# LED_ROWS.net
KiCad netlist of a schematic drawn in Altium Designer
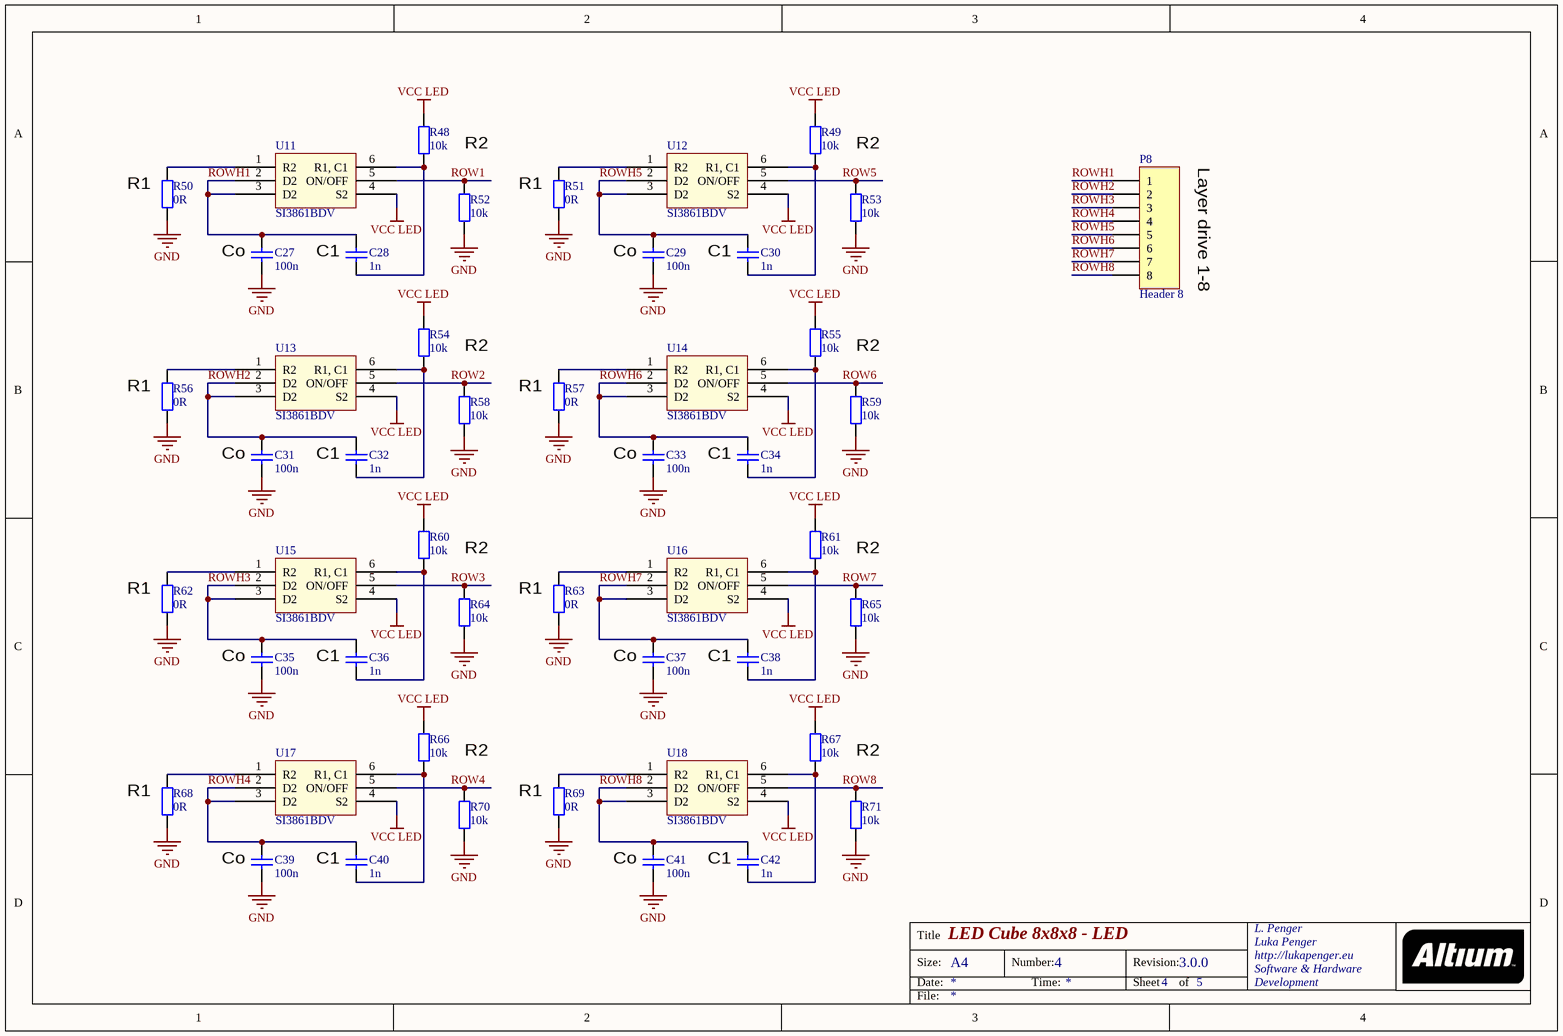
[diagram p0: LED_ROWS.SchDoc]

(export (version "E")
  (design (tool "Eeschema 10.0.6"))
  (components
    (comp (ref "C27")
      (value "100n")
      (footprint "1608[0603]")
      (description "Capacitor")
      (fields (field (name "PUBLISHER") "Altium Limited"))
      (libsource (lib "Miscellaneous Devices") (part "Cap"))
    )
    (comp (ref "C28")
      (value "1n")
      (footprint "1608[0603]")
      (description "Capacitor")
      (fields (field (name "PUBLISHER") "Altium Limited"))
      (libsource (lib "Miscellaneous Devices") (part "Cap"))
    )
    (comp (ref "C29")
      (value "100n")
      (footprint "1608[0603]")
      (description "Capacitor")
      (fields (field (name "PUBLISHER") "Altium Limited"))
      (libsource (lib "Miscellaneous Devices") (part "Cap"))
    )
    (comp (ref "C30")
      (value "1n")
      (footprint "1608[0603]")
      (description "Capacitor")
      (fields (field (name "PUBLISHER") "Altium Limited"))
      (libsource (lib "Miscellaneous Devices") (part "Cap"))
    )
    (comp (ref "C31")
      (value "100n")
      (footprint "1608[0603]")
      (description "Capacitor")
      (fields (field (name "PUBLISHER") "Altium Limited"))
      (libsource (lib "Miscellaneous Devices") (part "Cap"))
    )
    (comp (ref "C32")
      (value "1n")
      (footprint "1608[0603]")
      (description "Capacitor")
      (fields (field (name "PUBLISHER") "Altium Limited"))
      (libsource (lib "Miscellaneous Devices") (part "Cap"))
    )
    (comp (ref "C33")
      (value "100n")
      (footprint "1608[0603]")
      (description "Capacitor")
      (fields (field (name "PUBLISHER") "Altium Limited"))
      (libsource (lib "Miscellaneous Devices") (part "Cap"))
    )
    (comp (ref "C34")
      (value "1n")
      (footprint "1608[0603]")
      (description "Capacitor")
      (fields (field (name "PUBLISHER") "Altium Limited"))
      (libsource (lib "Miscellaneous Devices") (part "Cap"))
    )
    (comp (ref "C35")
      (value "100n")
      (footprint "1608[0603]")
      (description "Capacitor")
      (fields (field (name "PUBLISHER") "Altium Limited"))
      (libsource (lib "Miscellaneous Devices") (part "Cap"))
    )
    (comp (ref "C36")
      (value "1n")
      (footprint "1608[0603]")
      (description "Capacitor")
      (fields (field (name "PUBLISHER") "Altium Limited"))
      (libsource (lib "Miscellaneous Devices") (part "Cap"))
    )
    (comp (ref "C37")
      (value "100n")
      (footprint "1608[0603]")
      (description "Capacitor")
      (fields (field (name "PUBLISHER") "Altium Limited"))
      (libsource (lib "Miscellaneous Devices") (part "Cap"))
    )
    (comp (ref "C38")
      (value "1n")
      (footprint "1608[0603]")
      (description "Capacitor")
      (fields (field (name "PUBLISHER") "Altium Limited"))
      (libsource (lib "Miscellaneous Devices") (part "Cap"))
    )
    (comp (ref "C39")
      (value "100n")
      (footprint "1608[0603]")
      (description "Capacitor")
      (fields (field (name "PUBLISHER") "Altium Limited"))
      (libsource (lib "Miscellaneous Devices") (part "Cap"))
    )
    (comp (ref "C40")
      (value "1n")
      (footprint "1608[0603]")
      (description "Capacitor")
      (fields (field (name "PUBLISHER") "Altium Limited"))
      (libsource (lib "Miscellaneous Devices") (part "Cap"))
    )
    (comp (ref "C41")
      (value "100n")
      (footprint "1608[0603]")
      (description "Capacitor")
      (fields (field (name "PUBLISHER") "Altium Limited"))
      (libsource (lib "Miscellaneous Devices") (part "Cap"))
    )
    (comp (ref "C42")
      (value "1n")
      (footprint "1608[0603]")
      (description "Capacitor")
      (fields (field (name "PUBLISHER") "Altium Limited"))
      (libsource (lib "Miscellaneous Devices") (part "Cap"))
    )
    (comp (ref "P8")
      (value "Header 8")
      (footprint "IDC-2x4")
      (description "Header, 8-Pin")
      (fields (field (name "PUBLISHER") "Altium Limited"))
      (libsource (lib "Miscellaneous Connectors") (part "Header 8"))
    )
    (comp (ref "R48")
      (value "10k")
      (footprint "1608[0603]")
      (description "Resistor")
      (fields (field (name "PUBLISHER") "Altium Limited"))
      (libsource (lib "") (part "Res2_1"))
    )
    (comp (ref "R49")
      (value "10k")
      (footprint "1608[0603]")
      (description "Resistor")
      (fields (field (name "PUBLISHER") "Altium Limited"))
      (libsource (lib "") (part "Res2_1"))
    )
    (comp (ref "R50")
      (value "0R")
      (footprint "1608[0603]")
      (description "Resistor")
      (fields (field (name "PUBLISHER") "Altium Limited"))
      (libsource (lib "Miscellaneous Devices") (part "Res2"))
    )
    (comp (ref "R51")
      (value "0R")
      (footprint "1608[0603]")
      (description "Resistor")
      (fields (field (name "PUBLISHER") "Altium Limited"))
      (libsource (lib "Miscellaneous Devices") (part "Res2"))
    )
    (comp (ref "R52")
      (value "10k")
      (footprint "1608[0603]")
      (description "Resistor")
      (fields (field (name "PUBLISHER") "Altium Limited"))
      (libsource (lib "") (part "Res2_1"))
    )
    (comp (ref "R53")
      (value "10k")
      (footprint "1608[0603]")
      (description "Resistor")
      (fields (field (name "PUBLISHER") "Altium Limited"))
      (libsource (lib "") (part "Res2_1"))
    )
    (comp (ref "R54")
      (value "10k")
      (footprint "1608[0603]")
      (description "Resistor")
      (fields (field (name "PUBLISHER") "Altium Limited"))
      (libsource (lib "") (part "Res2_1"))
    )
    (comp (ref "R55")
      (value "10k")
      (footprint "1608[0603]")
      (description "Resistor")
      (fields (field (name "PUBLISHER") "Altium Limited"))
      (libsource (lib "") (part "Res2_1"))
    )
    (comp (ref "R56")
      (value "0R")
      (footprint "1608[0603]")
      (description "Resistor")
      (fields (field (name "PUBLISHER") "Altium Limited"))
      (libsource (lib "Miscellaneous Devices") (part "Res2"))
    )
    (comp (ref "R57")
      (value "0R")
      (footprint "1608[0603]")
      (description "Resistor")
      (fields (field (name "PUBLISHER") "Altium Limited"))
      (libsource (lib "Miscellaneous Devices") (part "Res2"))
    )
    (comp (ref "R58")
      (value "10k")
      (footprint "1608[0603]")
      (description "Resistor")
      (fields (field (name "PUBLISHER") "Altium Limited"))
      (libsource (lib "") (part "Res2_1"))
    )
    (comp (ref "R59")
      (value "10k")
      (footprint "1608[0603]")
      (description "Resistor")
      (fields (field (name "PUBLISHER") "Altium Limited"))
      (libsource (lib "") (part "Res2_1"))
    )
    (comp (ref "R60")
      (value "10k")
      (footprint "1608[0603]")
      (description "Resistor")
      (fields (field (name "PUBLISHER") "Altium Limited"))
      (libsource (lib "") (part "Res2_1"))
    )
    (comp (ref "R61")
      (value "10k")
      (footprint "1608[0603]")
      (description "Resistor")
      (fields (field (name "PUBLISHER") "Altium Limited"))
      (libsource (lib "") (part "Res2_1"))
    )
    (comp (ref "R62")
      (value "0R")
      (footprint "1608[0603]")
      (description "Resistor")
      (fields (field (name "PUBLISHER") "Altium Limited"))
      (libsource (lib "Miscellaneous Devices") (part "Res2"))
    )
    (comp (ref "R63")
      (value "0R")
      (footprint "1608[0603]")
      (description "Resistor")
      (fields (field (name "PUBLISHER") "Altium Limited"))
      (libsource (lib "Miscellaneous Devices") (part "Res2"))
    )
    (comp (ref "R64")
      (value "10k")
      (footprint "1608[0603]")
      (description "Resistor")
      (fields (field (name "PUBLISHER") "Altium Limited"))
      (libsource (lib "") (part "Res2_1"))
    )
    (comp (ref "R65")
      (value "10k")
      (footprint "1608[0603]")
      (description "Resistor")
      (fields (field (name "PUBLISHER") "Altium Limited"))
      (libsource (lib "") (part "Res2_1"))
    )
    (comp (ref "R66")
      (value "10k")
      (footprint "1608[0603]")
      (description "Resistor")
      (fields (field (name "PUBLISHER") "Altium Limited"))
      (libsource (lib "") (part "Res2_1"))
    )
    (comp (ref "R67")
      (value "10k")
      (footprint "1608[0603]")
      (description "Resistor")
      (fields (field (name "PUBLISHER") "Altium Limited"))
      (libsource (lib "") (part "Res2_1"))
    )
    (comp (ref "R68")
      (value "0R")
      (footprint "1608[0603]")
      (description "Resistor")
      (fields (field (name "PUBLISHER") "Altium Limited"))
      (libsource (lib "Miscellaneous Devices") (part "Res2"))
    )
    (comp (ref "R69")
      (value "0R")
      (footprint "1608[0603]")
      (description "Resistor")
      (fields (field (name "PUBLISHER") "Altium Limited"))
      (libsource (lib "Miscellaneous Devices") (part "Res2"))
    )
    (comp (ref "R70")
      (value "10k")
      (footprint "1608[0603]")
      (description "Resistor")
      (fields (field (name "PUBLISHER") "Altium Limited"))
      (libsource (lib "") (part "Res2_1"))
    )
    (comp (ref "R71")
      (value "10k")
      (footprint "1608[0603]")
      (description "Resistor")
      (fields (field (name "PUBLISHER") "Altium Limited"))
      (libsource (lib "") (part "Res2_1"))
    )
    (comp (ref "U11")
      (value "SI3861BDV")
      (footprint "TSOP 6")
      (description "4.5 - 20V 2.3A Load Switch")
      (libsource (lib "LukaLIBRARY") (part "SI3861BDV"))
    )
    (comp (ref "U12")
      (value "SI3861BDV")
      (footprint "TSOP 6")
      (description "4.5 - 20V 2.3A Load Switch")
      (libsource (lib "LukaLIBRARY") (part "SI3861BDV"))
    )
    (comp (ref "U13")
      (value "SI3861BDV")
      (footprint "TSOP 6")
      (description "4.5 - 20V 2.3A Load Switch")
      (libsource (lib "LukaLIBRARY") (part "SI3861BDV"))
    )
    (comp (ref "U14")
      (value "SI3861BDV")
      (footprint "TSOP 6")
      (description "4.5 - 20V 2.3A Load Switch")
      (libsource (lib "LukaLIBRARY") (part "SI3861BDV"))
    )
    (comp (ref "U15")
      (value "SI3861BDV")
      (footprint "TSOP 6")
      (description "4.5 - 20V 2.3A Load Switch")
      (libsource (lib "LukaLIBRARY") (part "SI3861BDV"))
    )
    (comp (ref "U16")
      (value "SI3861BDV")
      (footprint "TSOP 6")
      (description "4.5 - 20V 2.3A Load Switch")
      (libsource (lib "LukaLIBRARY") (part "SI3861BDV"))
    )
    (comp (ref "U17")
      (value "SI3861BDV")
      (footprint "TSOP 6")
      (description "4.5 - 20V 2.3A Load Switch")
      (libsource (lib "LukaLIBRARY") (part "SI3861BDV"))
    )
    (comp (ref "U18")
      (value "SI3861BDV")
      (footprint "TSOP 6")
      (description "4.5 - 20V 2.3A Load Switch")
      (libsource (lib "LukaLIBRARY") (part "SI3861BDV"))
    )
  )
  (nets
    (net (code "1") (name "/ROW1") (class "Default")
      (node (ref "R52") (pin "2") (pinfunction "2_2") (pintype "passive"))
      (node (ref "U11") (pin "5") (pinfunction "ON/OFF_5") (pintype "passive"))
    )
    (net (code "2") (name "/ROW2") (class "Default")
      (node (ref "R58") (pin "2") (pinfunction "2_2") (pintype "passive"))
      (node (ref "U13") (pin "5") (pinfunction "ON/OFF_5") (pintype "passive"))
    )
    (net (code "3") (name "/ROW3") (class "Default")
      (node (ref "R64") (pin "2") (pinfunction "2_2") (pintype "passive"))
      (node (ref "U15") (pin "5") (pinfunction "ON/OFF_5") (pintype "passive"))
    )
    (net (code "4") (name "/ROW4") (class "Default")
      (node (ref "R70") (pin "2") (pinfunction "2_2") (pintype "passive"))
      (node (ref "U17") (pin "5") (pinfunction "ON/OFF_5") (pintype "passive"))
    )
    (net (code "5") (name "/ROW5") (class "Default")
      (node (ref "R53") (pin "2") (pinfunction "2_2") (pintype "passive"))
      (node (ref "U12") (pin "5") (pinfunction "ON/OFF_5") (pintype "passive"))
    )
    (net (code "6") (name "/ROW6") (class "Default")
      (node (ref "R59") (pin "2") (pinfunction "2_2") (pintype "passive"))
      (node (ref "U14") (pin "5") (pinfunction "ON/OFF_5") (pintype "passive"))
    )
    (net (code "7") (name "/ROW7") (class "Default")
      (node (ref "R65") (pin "2") (pinfunction "2_2") (pintype "passive"))
      (node (ref "U16") (pin "5") (pinfunction "ON/OFF_5") (pintype "passive"))
    )
    (net (code "8") (name "/ROW8") (class "Default")
      (node (ref "R71") (pin "2") (pinfunction "2_2") (pintype "passive"))
      (node (ref "U18") (pin "5") (pinfunction "ON/OFF_5") (pintype "passive"))
    )
    (net (code "9") (name "/ROWH1") (class "Default")
      (node (ref "C27") (pin "1") (pinfunction "1_1") (pintype "passive"))
      (node (ref "C28") (pin "1") (pinfunction "1_1") (pintype "passive"))
      (node (ref "P8") (pin "1") (pinfunction "1_1") (pintype "passive"))
      (node (ref "U11") (pin "2") (pinfunction "D2_2") (pintype "passive"))
      (node (ref "U11") (pin "3") (pinfunction "D2_3") (pintype "passive"))
    )
    (net (code "10") (name "/ROWH2") (class "Default")
      (node (ref "C31") (pin "1") (pinfunction "1_1") (pintype "passive"))
      (node (ref "C32") (pin "1") (pinfunction "1_1") (pintype "passive"))
      (node (ref "P8") (pin "2") (pinfunction "2_2") (pintype "passive"))
      (node (ref "U13") (pin "2") (pinfunction "D2_2") (pintype "passive"))
      (node (ref "U13") (pin "3") (pinfunction "D2_3") (pintype "passive"))
    )
    (net (code "11") (name "/ROWH3") (class "Default")
      (node (ref "C35") (pin "1") (pinfunction "1_1") (pintype "passive"))
      (node (ref "C36") (pin "1") (pinfunction "1_1") (pintype "passive"))
      (node (ref "P8") (pin "3") (pinfunction "3_3") (pintype "passive"))
      (node (ref "U15") (pin "2") (pinfunction "D2_2") (pintype "passive"))
      (node (ref "U15") (pin "3") (pinfunction "D2_3") (pintype "passive"))
    )
    (net (code "12") (name "/ROWH4") (class "Default")
      (node (ref "C39") (pin "1") (pinfunction "1_1") (pintype "passive"))
      (node (ref "C40") (pin "1") (pinfunction "1_1") (pintype "passive"))
      (node (ref "P8") (pin "4") (pinfunction "4_4") (pintype "passive"))
      (node (ref "U17") (pin "2") (pinfunction "D2_2") (pintype "passive"))
      (node (ref "U17") (pin "3") (pinfunction "D2_3") (pintype "passive"))
    )
    (net (code "13") (name "/ROWH5") (class "Default")
      (node (ref "C29") (pin "1") (pinfunction "1_1") (pintype "passive"))
      (node (ref "C30") (pin "1") (pinfunction "1_1") (pintype "passive"))
      (node (ref "P8") (pin "5") (pinfunction "5_5") (pintype "passive"))
      (node (ref "U12") (pin "2") (pinfunction "D2_2") (pintype "passive"))
      (node (ref "U12") (pin "3") (pinfunction "D2_3") (pintype "passive"))
    )
    (net (code "14") (name "/ROWH6") (class "Default")
      (node (ref "C33") (pin "1") (pinfunction "1_1") (pintype "passive"))
      (node (ref "C34") (pin "1") (pinfunction "1_1") (pintype "passive"))
      (node (ref "P8") (pin "6") (pinfunction "6_6") (pintype "passive"))
      (node (ref "U14") (pin "2") (pinfunction "D2_2") (pintype "passive"))
      (node (ref "U14") (pin "3") (pinfunction "D2_3") (pintype "passive"))
    )
    (net (code "15") (name "/ROWH7") (class "Default")
      (node (ref "C37") (pin "1") (pinfunction "1_1") (pintype "passive"))
      (node (ref "C38") (pin "1") (pinfunction "1_1") (pintype "passive"))
      (node (ref "P8") (pin "7") (pinfunction "7_7") (pintype "passive"))
      (node (ref "U16") (pin "2") (pinfunction "D2_2") (pintype "passive"))
      (node (ref "U16") (pin "3") (pinfunction "D2_3") (pintype "passive"))
    )
    (net (code "16") (name "/ROWH8") (class "Default")
      (node (ref "C41") (pin "1") (pinfunction "1_1") (pintype "passive"))
      (node (ref "C42") (pin "1") (pinfunction "1_1") (pintype "passive"))
      (node (ref "P8") (pin "8") (pinfunction "8_8") (pintype "passive"))
      (node (ref "U18") (pin "2") (pinfunction "D2_2") (pintype "passive"))
      (node (ref "U18") (pin "3") (pinfunction "D2_3") (pintype "passive"))
    )
    (net (code "17") (name "GND") (class "Default")
      (node (ref "C27") (pin "2") (pinfunction "2_2") (pintype "passive"))
      (node (ref "C29") (pin "2") (pinfunction "2_2") (pintype "passive"))
      (node (ref "C31") (pin "2") (pinfunction "2_2") (pintype "passive"))
      (node (ref "C33") (pin "2") (pinfunction "2_2") (pintype "passive"))
      (node (ref "C35") (pin "2") (pinfunction "2_2") (pintype "passive"))
      (node (ref "C37") (pin "2") (pinfunction "2_2") (pintype "passive"))
      (node (ref "C39") (pin "2") (pinfunction "2_2") (pintype "passive"))
      (node (ref "C41") (pin "2") (pinfunction "2_2") (pintype "passive"))
      (node (ref "R50") (pin "2") (pinfunction "2_2") (pintype "passive"))
      (node (ref "R51") (pin "2") (pinfunction "2_2") (pintype "passive"))
      (node (ref "R52") (pin "1") (pinfunction "1_1") (pintype "passive"))
      (node (ref "R53") (pin "1") (pinfunction "1_1") (pintype "passive"))
      (node (ref "R56") (pin "2") (pinfunction "2_2") (pintype "passive"))
      (node (ref "R57") (pin "2") (pinfunction "2_2") (pintype "passive"))
      (node (ref "R58") (pin "1") (pinfunction "1_1") (pintype "passive"))
      (node (ref "R59") (pin "1") (pinfunction "1_1") (pintype "passive"))
      (node (ref "R62") (pin "2") (pinfunction "2_2") (pintype "passive"))
      (node (ref "R63") (pin "2") (pinfunction "2_2") (pintype "passive"))
      (node (ref "R64") (pin "1") (pinfunction "1_1") (pintype "passive"))
      (node (ref "R65") (pin "1") (pinfunction "1_1") (pintype "passive"))
      (node (ref "R68") (pin "2") (pinfunction "2_2") (pintype "passive"))
      (node (ref "R69") (pin "2") (pinfunction "2_2") (pintype "passive"))
      (node (ref "R70") (pin "1") (pinfunction "1_1") (pintype "passive"))
      (node (ref "R71") (pin "1") (pinfunction "1_1") (pintype "passive"))
    )
    (net (code "18") (name "Net-(U11-R1,_C1)") (class "Default")
      (node (ref "C28") (pin "2") (pinfunction "2_2") (pintype "passive"))
      (node (ref "R48") (pin "1") (pinfunction "1_1") (pintype "passive"))
      (node (ref "U11") (pin "6") (pinfunction "R1,_C1_6") (pintype "passive"))
    )
    (net (code "19") (name "Net-(U11-R2)") (class "Default")
      (node (ref "R50") (pin "1") (pinfunction "1_1") (pintype "passive"))
      (node (ref "U11") (pin "1") (pinfunction "R2_1") (pintype "passive"))
    )
    (net (code "20") (name "Net-(U12-R1,_C1)") (class "Default")
      (node (ref "C30") (pin "2") (pinfunction "2_2") (pintype "passive"))
      (node (ref "R49") (pin "1") (pinfunction "1_1") (pintype "passive"))
      (node (ref "U12") (pin "6") (pinfunction "R1,_C1_6") (pintype "passive"))
    )
    (net (code "21") (name "Net-(U12-R2)") (class "Default")
      (node (ref "R51") (pin "1") (pinfunction "1_1") (pintype "passive"))
      (node (ref "U12") (pin "1") (pinfunction "R2_1") (pintype "passive"))
    )
    (net (code "22") (name "Net-(U13-R1,_C1)") (class "Default")
      (node (ref "C32") (pin "2") (pinfunction "2_2") (pintype "passive"))
      (node (ref "R54") (pin "1") (pinfunction "1_1") (pintype "passive"))
      (node (ref "U13") (pin "6") (pinfunction "R1,_C1_6") (pintype "passive"))
    )
    (net (code "23") (name "Net-(U13-R2)") (class "Default")
      (node (ref "R56") (pin "1") (pinfunction "1_1") (pintype "passive"))
      (node (ref "U13") (pin "1") (pinfunction "R2_1") (pintype "passive"))
    )
    (net (code "24") (name "Net-(U14-R1,_C1)") (class "Default")
      (node (ref "C34") (pin "2") (pinfunction "2_2") (pintype "passive"))
      (node (ref "R55") (pin "1") (pinfunction "1_1") (pintype "passive"))
      (node (ref "U14") (pin "6") (pinfunction "R1,_C1_6") (pintype "passive"))
    )
    (net (code "25") (name "Net-(U14-R2)") (class "Default")
      (node (ref "R57") (pin "1") (pinfunction "1_1") (pintype "passive"))
      (node (ref "U14") (pin "1") (pinfunction "R2_1") (pintype "passive"))
    )
    (net (code "26") (name "Net-(U15-R1,_C1)") (class "Default")
      (node (ref "C36") (pin "2") (pinfunction "2_2") (pintype "passive"))
      (node (ref "R60") (pin "1") (pinfunction "1_1") (pintype "passive"))
      (node (ref "U15") (pin "6") (pinfunction "R1,_C1_6") (pintype "passive"))
    )
    (net (code "27") (name "Net-(U15-R2)") (class "Default")
      (node (ref "R62") (pin "1") (pinfunction "1_1") (pintype "passive"))
      (node (ref "U15") (pin "1") (pinfunction "R2_1") (pintype "passive"))
    )
    (net (code "28") (name "Net-(U16-R1,_C1)") (class "Default")
      (node (ref "C38") (pin "2") (pinfunction "2_2") (pintype "passive"))
      (node (ref "R61") (pin "1") (pinfunction "1_1") (pintype "passive"))
      (node (ref "U16") (pin "6") (pinfunction "R1,_C1_6") (pintype "passive"))
    )
    (net (code "29") (name "Net-(U16-R2)") (class "Default")
      (node (ref "R63") (pin "1") (pinfunction "1_1") (pintype "passive"))
      (node (ref "U16") (pin "1") (pinfunction "R2_1") (pintype "passive"))
    )
    (net (code "30") (name "Net-(U17-R1,_C1)") (class "Default")
      (node (ref "C40") (pin "2") (pinfunction "2_2") (pintype "passive"))
      (node (ref "R66") (pin "1") (pinfunction "1_1") (pintype "passive"))
      (node (ref "U17") (pin "6") (pinfunction "R1,_C1_6") (pintype "passive"))
    )
    (net (code "31") (name "Net-(U17-R2)") (class "Default")
      (node (ref "R68") (pin "1") (pinfunction "1_1") (pintype "passive"))
      (node (ref "U17") (pin "1") (pinfunction "R2_1") (pintype "passive"))
    )
    (net (code "32") (name "Net-(U18-R1,_C1)") (class "Default")
      (node (ref "C42") (pin "2") (pinfunction "2_2") (pintype "passive"))
      (node (ref "R67") (pin "1") (pinfunction "1_1") (pintype "passive"))
      (node (ref "U18") (pin "6") (pinfunction "R1,_C1_6") (pintype "passive"))
    )
    (net (code "33") (name "Net-(U18-R2)") (class "Default")
      (node (ref "R69") (pin "1") (pinfunction "1_1") (pintype "passive"))
      (node (ref "U18") (pin "1") (pinfunction "R2_1") (pintype "passive"))
    )
    (net (code "34") (name "VCC LED") (class "Default")
      (node (ref "R48") (pin "2") (pinfunction "2_2") (pintype "passive"))
      (node (ref "R49") (pin "2") (pinfunction "2_2") (pintype "passive"))
      (node (ref "R54") (pin "2") (pinfunction "2_2") (pintype "passive"))
      (node (ref "R55") (pin "2") (pinfunction "2_2") (pintype "passive"))
      (node (ref "R60") (pin "2") (pinfunction "2_2") (pintype "passive"))
      (node (ref "R61") (pin "2") (pinfunction "2_2") (pintype "passive"))
      (node (ref "R66") (pin "2") (pinfunction "2_2") (pintype "passive"))
      (node (ref "R67") (pin "2") (pinfunction "2_2") (pintype "passive"))
      (node (ref "U11") (pin "4") (pinfunction "S2_4") (pintype "passive"))
      (node (ref "U12") (pin "4") (pinfunction "S2_4") (pintype "passive"))
      (node (ref "U13") (pin "4") (pinfunction "S2_4") (pintype "passive"))
      (node (ref "U14") (pin "4") (pinfunction "S2_4") (pintype "passive"))
      (node (ref "U15") (pin "4") (pinfunction "S2_4") (pintype "passive"))
      (node (ref "U16") (pin "4") (pinfunction "S2_4") (pintype "passive"))
      (node (ref "U17") (pin "4") (pinfunction "S2_4") (pintype "passive"))
      (node (ref "U18") (pin "4") (pinfunction "S2_4") (pintype "passive"))
    )
  )
)
